# ESP12F.net
KiCad netlist of a schematic drawn in Altium Designer
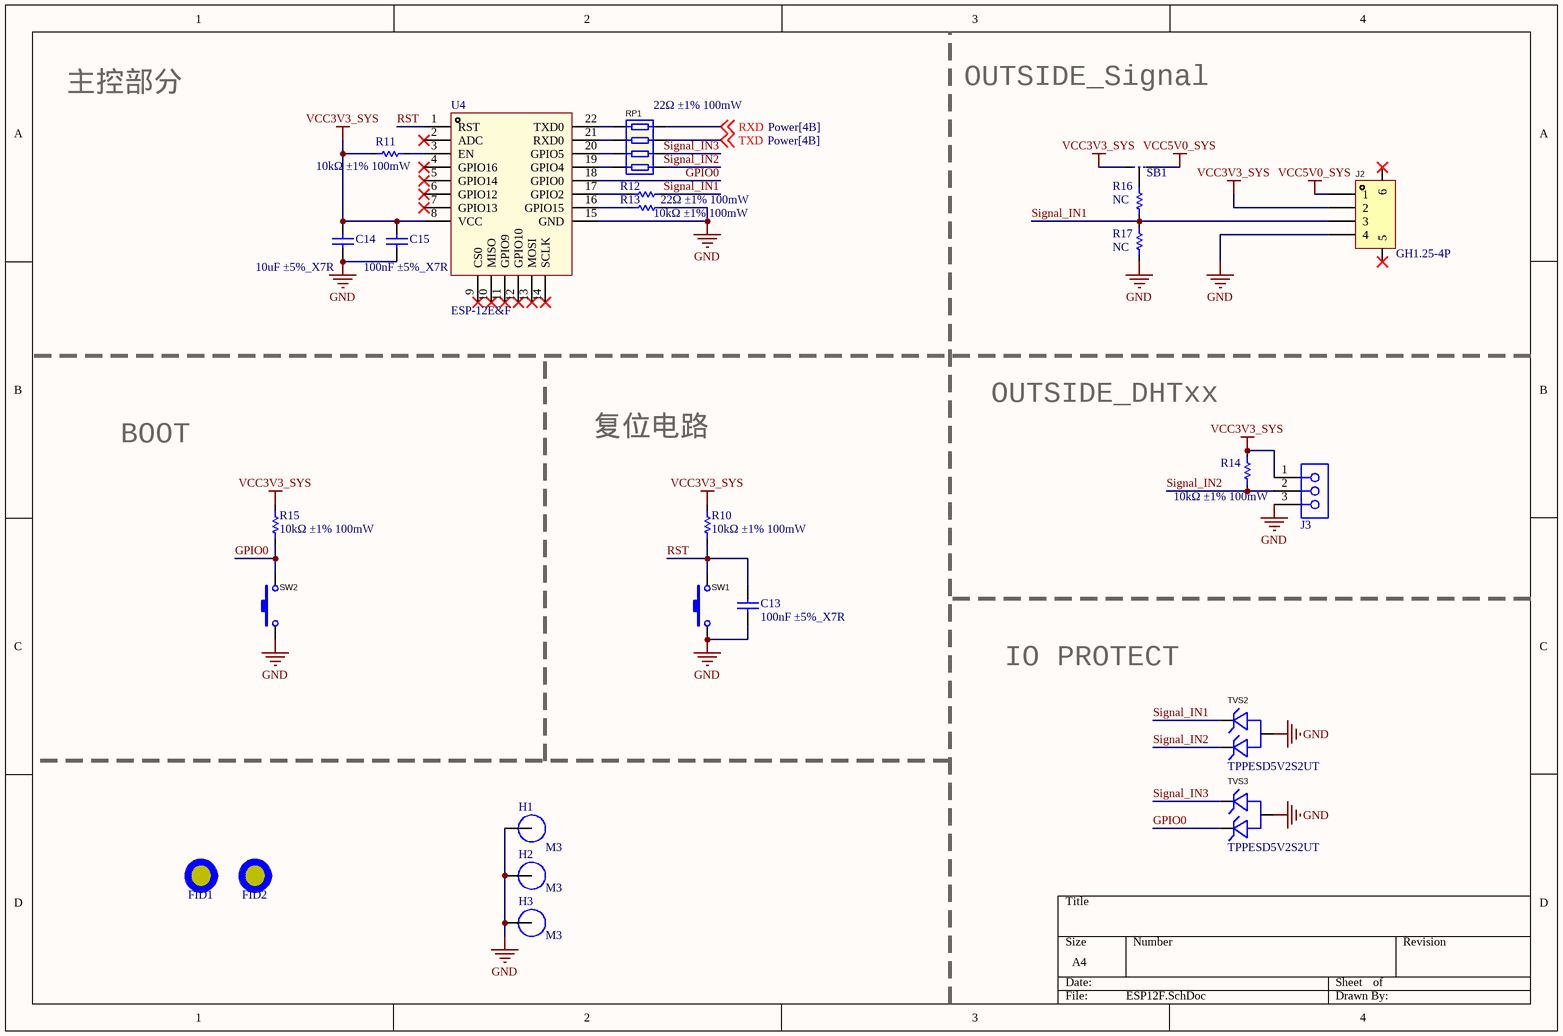
[diagram p0: ESP12F.SchDoc]

(export (version "E")
  (design (tool "Eeschema 10.0.6"))
  (components
    (comp (ref "C13")
      (value "100nF ±5%_X7R")
      (footprint "C0603")
      (description "Capacitor")
      (fields (field (name "PUBLISHER") "Altium Limited"))
      (libsource (lib "Component_Footprints") (part "Cap"))
    )
    (comp (ref "C14")
      (value "10uF ±5%_X7R")
      (footprint "C0603")
      (description "Capacitor")
      (fields (field (name "PUBLISHER") "Altium Limited"))
      (libsource (lib "Component_Footprints") (part "Cap"))
    )
    (comp (ref "C15")
      (value "100nF ±5%_X7R")
      (footprint "C0603")
      (description "Capacitor")
      (fields (field (name "PUBLISHER") "Altium Limited"))
      (libsource (lib "Component_Footprints") (part "Cap"))
    )
    (comp (ref "FID1")
      (value "MARK Point")
      (footprint "FIDUCIAL")
      (description "1mm Fiducial with 2mm soldermask, 3mm keepout")
      (libsource (lib "Component") (part "FIDUCIAL"))
    )
    (comp (ref "FID2")
      (value "MARK Point")
      (footprint "FIDUCIAL")
      (description "1mm Fiducial with 2mm soldermask, 3mm keepout")
      (libsource (lib "Component") (part "FIDUCIAL"))
    )
    (comp (ref "H1")
      (value "M3")
      (footprint "M3_PTH")
      (description "Hole with copper")
      (libsource (lib "Component") (part "PTH"))
    )
    (comp (ref "H2")
      (value "M3")
      (footprint "M3_PTH")
      (description "Hole with copper")
      (libsource (lib "Component") (part "PTH"))
    )
    (comp (ref "H3")
      (value "M3")
      (footprint "M3_PTH")
      (description "Hole with copper")
      (libsource (lib "Component") (part "PTH"))
    )
    (comp (ref "J2")
      (value "GH1.25-4P")
      (footprint "GH1.25-4P")
      (fields
        (field (name "MANUFACTURER") "BOOMELE(博穆精密)")
        (field (name "MANUFACTURER PART") "GH1.25-5PLTPZ")
      )
      (libsource (lib "Connectivity_Plugs") (part "GH1.25-4P"))
    )
    (comp (ref "J3")
      (value "61300311821")
      (footprint "61300311821")
      (description "WR-PHD Socket Header, THT, Vertical, pitch 2.54mm, 1 Row, 3P")
      (fields (field (name "MANUFACTURER") "Wurth Elektronik"))
      (libsource (lib "Altium_WR-PHD (rev22b)") (part "61300311821"))
    )
    (comp (ref "R10")
      (value "10kΩ ±1% 100mW")
      (footprint "R0402")
      (description "Resistor")
      (fields (field (name "PUBLISHER") "Altium Limited"))
      (libsource (lib "Component_Footprints") (part "Res"))
    )
    (comp (ref "R11")
      (value "10kΩ ±1% 100mW")
      (footprint "R0402")
      (description "Resistor")
      (fields (field (name "PUBLISHER") "Altium Limited"))
      (libsource (lib "Component") (part "Res"))
    )
    (comp (ref "R12")
      (value "22Ω ±1% 100mW")
      (footprint "R0402")
      (description "Resistor")
      (fields (field (name "PUBLISHER") "Altium Limited"))
      (libsource (lib "Component") (part "Res"))
    )
    (comp (ref "R13")
      (value "10kΩ ±1% 100mW")
      (footprint "R0402")
      (description "Resistor")
      (fields (field (name "PUBLISHER") "Altium Limited"))
      (libsource (lib "Component") (part "Res"))
    )
    (comp (ref "R14")
      (value "10kΩ ±1% 100mW")
      (footprint "R0402")
      (description "Resistor")
      (fields (field (name "PUBLISHER") "Altium Limited"))
      (libsource (lib "Component_Footprints") (part "Res"))
    )
    (comp (ref "R15")
      (value "10kΩ ±1% 100mW")
      (footprint "R0402")
      (description "Resistor")
      (fields (field (name "PUBLISHER") "Altium Limited"))
      (libsource (lib "Component_Footprints") (part "Res"))
    )
    (comp (ref "R16")
      (value "NC")
      (footprint "R0402")
      (description "Resistor")
      (fields (field (name "PUBLISHER") "Altium Limited"))
      (libsource (lib "Component_Footprints") (part "Res"))
    )
    (comp (ref "R17")
      (value "NC")
      (footprint "R0402")
      (description "Resistor")
      (fields (field (name "PUBLISHER") "Altium Limited"))
      (libsource (lib "Component_Footprints") (part "Res"))
    )
    (comp (ref "RP1")
      (value "22Ω ±1% 100mW")
      (footprint "RES-ARRAY-SMD_0603-8P-L3.2-W1.6-BL")
      (fields
        (field (name "MANUFACTURER") "YAGEO(国巨)")
        (field (name "MANUFACTURER PART") "YC124-JR-0730RL")
        (field (name "TOLERANCE") "±5%")
      )
      (libsource (lib "Component_Footprints") (part "RP"))
    )
    (comp (ref "SB1")
      (value "SHORT_3")
      (footprint "SHORT_3_180deg")
      (libsource (lib "Component") (part "SHORT_3"))
    )
    (comp (ref "SW1")
      (value "TS-1185-B-A-B-A")
      (footprint "SW-SMD_L4.0-W3.0-LS5.0")
      (description "触点电流：50mA 额定电压(DC)：12V 电路结构：单刀单掷 安装方式：立贴 带灯：无 作用力：160gf 机械寿命：10万次 带支架：否 轻触开关3x4x2贴片2脚小龟 160gf")
      (fields (field (name "MANUFACTURER") "XKB Connectivity(中国星坤)"))
      (libsource (lib "Component_Footprints") (part "Button"))
    )
    (comp (ref "SW2")
      (value "TS-1185-B-A-B-A")
      (footprint "SW-SMD_L4.0-W3.0-LS5.0")
      (description "触点电流：50mA 额定电压(DC)：12V 电路结构：单刀单掷 安装方式：立贴 带灯：无 作用力：160gf 机械寿命：10万次 带支架：否 轻触开关3x4x2贴片2脚小龟 160gf")
      (fields (field (name "MANUFACTURER") "XKB Connectivity(中国星坤)"))
      (libsource (lib "Component_Footprints") (part "Button"))
    )
    (comp (ref "TVS2")
      (value "TPPESD5V2S2UT")
      (footprint "SOT-23-3_L2.9-W1.3-P1.90-LS2.4-BR")
      (fields (field (name "MANUFACTURER") "TECH PUBLIC(台舟)"))
      (libsource (lib "Component") (part "TVS"))
    )
    (comp (ref "TVS3")
      (value "TPPESD5V2S2UT")
      (footprint "SOT-23-3_L2.9-W1.3-P1.90-LS2.4-BR")
      (fields (field (name "MANUFACTURER") "TECH PUBLIC(台舟)"))
      (libsource (lib "Component") (part "TVS"))
    )
    (comp (ref "U4")
      (value "ESP-12E&F")
      (footprint "ESP-12E")
      (description "ESP-12E&F Onboard Module")
      (libsource (lib "Common_Modules") (part "ESP-12E&F"))
    )
  )
  (nets
    (net (code "1") (name "/GPIO0") (class "Default")
      (node (ref "R15") (pin "1") (pinfunction "1_1") (pintype "passive"))
      (node (ref "SW2") (pin "2") (pinfunction "2_2") (pintype "passive"))
      (node (ref "TVS3") (pin "1") (pinfunction "A_1") (pintype "passive"))
      (node (ref "U4") (pin "18") (pinfunction "GPIO0_18") (pintype "passive"))
    )
    (net (code "2") (name "/RST") (class "Default")
      (node (ref "C13") (pin "2") (pinfunction "2_2") (pintype "passive"))
      (node (ref "R10") (pin "1") (pinfunction "1_1") (pintype "passive"))
      (node (ref "SW1") (pin "2") (pinfunction "2_2") (pintype "passive"))
      (node (ref "U4") (pin "1") (pinfunction "RST_1") (pintype "passive"))
    )
    (net (code "3") (name "/Signal_IN1") (class "Default")
      (node (ref "J2") (pin "3") (pinfunction "3_3") (pintype "passive"))
      (node (ref "R12") (pin "2") (pinfunction "2_2") (pintype "passive"))
      (node (ref "R16") (pin "1") (pinfunction "1_1") (pintype "passive"))
      (node (ref "R17") (pin "2") (pinfunction "2_2") (pintype "passive"))
      (node (ref "TVS2") (pin "2") (pinfunction "A_2") (pintype "passive"))
    )
    (net (code "4") (name "/Signal_IN2") (class "Default")
      (node (ref "J3") (pin "2") (pinfunction "2_2") (pintype "passive"))
      (node (ref "R14") (pin "1") (pinfunction "1_1") (pintype "passive"))
      (node (ref "RP1") (pin "1") (pinfunction "1_1") (pintype "passive"))
      (node (ref "TVS2") (pin "1") (pinfunction "A_1") (pintype "passive"))
    )
    (net (code "5") (name "/Signal_IN3") (class "Default")
      (node (ref "RP1") (pin "2") (pinfunction "2_2") (pintype "passive"))
      (node (ref "TVS3") (pin "2") (pinfunction "A_2") (pintype "passive"))
    )
    (net (code "6") (name "GND") (class "Default")
      (node (ref "C13") (pin "1") (pinfunction "1_1") (pintype "passive"))
      (node (ref "C14") (pin "1") (pinfunction "1_1") (pintype "passive"))
      (node (ref "C15") (pin "1") (pinfunction "1_1") (pintype "passive"))
      (node (ref "H1") (pin "1") (pinfunction "1_1") (pintype "passive"))
      (node (ref "H2") (pin "1") (pinfunction "1_1") (pintype "passive"))
      (node (ref "H3") (pin "1") (pinfunction "1_1") (pintype "passive"))
      (node (ref "J2") (pin "4") (pinfunction "4_4") (pintype "passive"))
      (node (ref "J3") (pin "3") (pinfunction "3_3") (pintype "passive"))
      (node (ref "R13") (pin "2") (pinfunction "2_2") (pintype "passive"))
      (node (ref "R17") (pin "1") (pinfunction "1_1") (pintype "passive"))
      (node (ref "SW1") (pin "1") (pinfunction "1_1") (pintype "passive"))
      (node (ref "SW2") (pin "1") (pinfunction "1_1") (pintype "passive"))
      (node (ref "TVS2") (pin "3") (pinfunction "K_3") (pintype "passive"))
      (node (ref "TVS3") (pin "3") (pinfunction "K_3") (pintype "passive"))
      (node (ref "U4") (pin "15") (pinfunction "GND_15") (pintype "passive"))
    )
    (net (code "7") (name "Net-(R16-Pad2)") (class "Default")
      (node (ref "R16") (pin "2") (pinfunction "2_2") (pintype "passive"))
      (node (ref "SB1") (pin "3") (pinfunction "3_3") (pintype "passive"))
    )
    (net (code "8") (name "Net-(U4-EN)") (class "Default")
      (node (ref "R11") (pin "2") (pinfunction "2_2") (pintype "passive"))
      (node (ref "U4") (pin "3") (pinfunction "EN_3") (pintype "passive"))
    )
    (net (code "9") (name "Net-(U4-GPIO2)") (class "Default")
      (node (ref "R12") (pin "1") (pinfunction "1_1") (pintype "passive"))
      (node (ref "U4") (pin "17") (pinfunction "GPIO2_17") (pintype "passive"))
    )
    (net (code "10") (name "Net-(U4-GPIO4)") (class "Default")
      (node (ref "RP1") (pin "8") (pinfunction "8_8") (pintype "passive"))
      (node (ref "U4") (pin "19") (pinfunction "GPIO4_19") (pintype "passive"))
    )
    (net (code "11") (name "Net-(U4-GPIO5)") (class "Default")
      (node (ref "RP1") (pin "7") (pinfunction "7_7") (pintype "passive"))
      (node (ref "U4") (pin "20") (pinfunction "GPIO5_20") (pintype "passive"))
    )
    (net (code "12") (name "Net-(U4-GPIO15)") (class "Default")
      (node (ref "R13") (pin "1") (pinfunction "1_1") (pintype "passive"))
      (node (ref "U4") (pin "16") (pinfunction "GPIO15_16") (pintype "passive"))
    )
    (net (code "13") (name "Net-(U4-RXD0)") (class "Default")
      (node (ref "RP1") (pin "6") (pinfunction "6_6") (pintype "passive"))
      (node (ref "U4") (pin "21") (pinfunction "RXD0_21") (pintype "passive"))
    )
    (net (code "14") (name "Net-(U4-TXD0)") (class "Default")
      (node (ref "RP1") (pin "5") (pinfunction "5_5") (pintype "passive"))
      (node (ref "U4") (pin "22") (pinfunction "TXD0_22") (pintype "passive"))
    )
    (net (code "15") (name "RXD") (class "Default")
      (node (ref "RP1") (pin "4") (pinfunction "4_4") (pintype "passive"))
    )
    (net (code "16") (name "TXD") (class "Default")
      (node (ref "RP1") (pin "3") (pinfunction "3_3") (pintype "passive"))
    )
    (net (code "17") (name "VCC3V3_SYS") (class "Default")
      (node (ref "C14") (pin "2") (pinfunction "2_2") (pintype "passive"))
      (node (ref "C15") (pin "2") (pinfunction "2_2") (pintype "passive"))
      (node (ref "J2") (pin "2") (pinfunction "2_2") (pintype "passive"))
      (node (ref "J3") (pin "1") (pinfunction "1_1") (pintype "passive"))
      (node (ref "R10") (pin "2") (pinfunction "2_2") (pintype "passive"))
      (node (ref "R11") (pin "1") (pinfunction "1_1") (pintype "passive"))
      (node (ref "R14") (pin "2") (pinfunction "2_2") (pintype "passive"))
      (node (ref "R15") (pin "2") (pinfunction "2_2") (pintype "passive"))
      (node (ref "SB1") (pin "1") (pinfunction "1_1") (pintype "passive"))
      (node (ref "U4") (pin "8") (pinfunction "VCC_8") (pintype "passive"))
    )
    (net (code "18") (name "VCC5V0_SYS") (class "Default")
      (node (ref "J2") (pin "1") (pinfunction "1_1") (pintype "passive"))
      (node (ref "SB1") (pin "2") (pinfunction "2_2") (pintype "passive"))
    )
    (net (code "19") (name "unconnected-(J2-Pad5)") (class "Default")
      (node (ref "J2") (pin "5") (pinfunction "5_5") (pintype "passive+no_connect"))
    )
    (net (code "20") (name "unconnected-(J2-Pad6)") (class "Default")
      (node (ref "J2") (pin "6") (pinfunction "6_6") (pintype "passive+no_connect"))
    )
    (net (code "21") (name "unconnected-(U4-ADC-Pad2)") (class "Default")
      (node (ref "U4") (pin "2") (pinfunction "ADC_2") (pintype "passive+no_connect"))
    )
    (net (code "22") (name "unconnected-(U4-CS0-Pad9)") (class "Default")
      (node (ref "U4") (pin "9") (pinfunction "CS0_9") (pintype "passive+no_connect"))
    )
    (net (code "23") (name "unconnected-(U4-GPIO9-Pad11)") (class "Default")
      (node (ref "U4") (pin "11") (pinfunction "GPIO9_11") (pintype "passive+no_connect"))
    )
    (net (code "24") (name "unconnected-(U4-GPIO10-Pad12)") (class "Default")
      (node (ref "U4") (pin "12") (pinfunction "GPIO10_12") (pintype "passive+no_connect"))
    )
    (net (code "25") (name "unconnected-(U4-GPIO12-Pad6)") (class "Default")
      (node (ref "U4") (pin "6") (pinfunction "GPIO12_6") (pintype "passive+no_connect"))
    )
    (net (code "26") (name "unconnected-(U4-GPIO13-Pad7)") (class "Default")
      (node (ref "U4") (pin "7") (pinfunction "GPIO13_7") (pintype "passive+no_connect"))
    )
    (net (code "27") (name "unconnected-(U4-GPIO14-Pad5)") (class "Default")
      (node (ref "U4") (pin "5") (pinfunction "GPIO14_5") (pintype "passive+no_connect"))
    )
    (net (code "28") (name "unconnected-(U4-GPIO16-Pad4)") (class "Default")
      (node (ref "U4") (pin "4") (pinfunction "GPIO16_4") (pintype "passive+no_connect"))
    )
    (net (code "29") (name "unconnected-(U4-MISO-Pad10)") (class "Default")
      (node (ref "U4") (pin "10") (pinfunction "MISO_10") (pintype "passive+no_connect"))
    )
    (net (code "30") (name "unconnected-(U4-MOSI-Pad13)") (class "Default")
      (node (ref "U4") (pin "13") (pinfunction "MOSI_13") (pintype "passive+no_connect"))
    )
    (net (code "31") (name "unconnected-(U4-SCLK-Pad14)") (class "Default")
      (node (ref "U4") (pin "14") (pinfunction "SCLK_14") (pintype "passive+no_connect"))
    )
  )
)
